# ProProject_GD32__2024-05-09.net
KiCad netlist of a schematic drawn in EasyEDA Pro
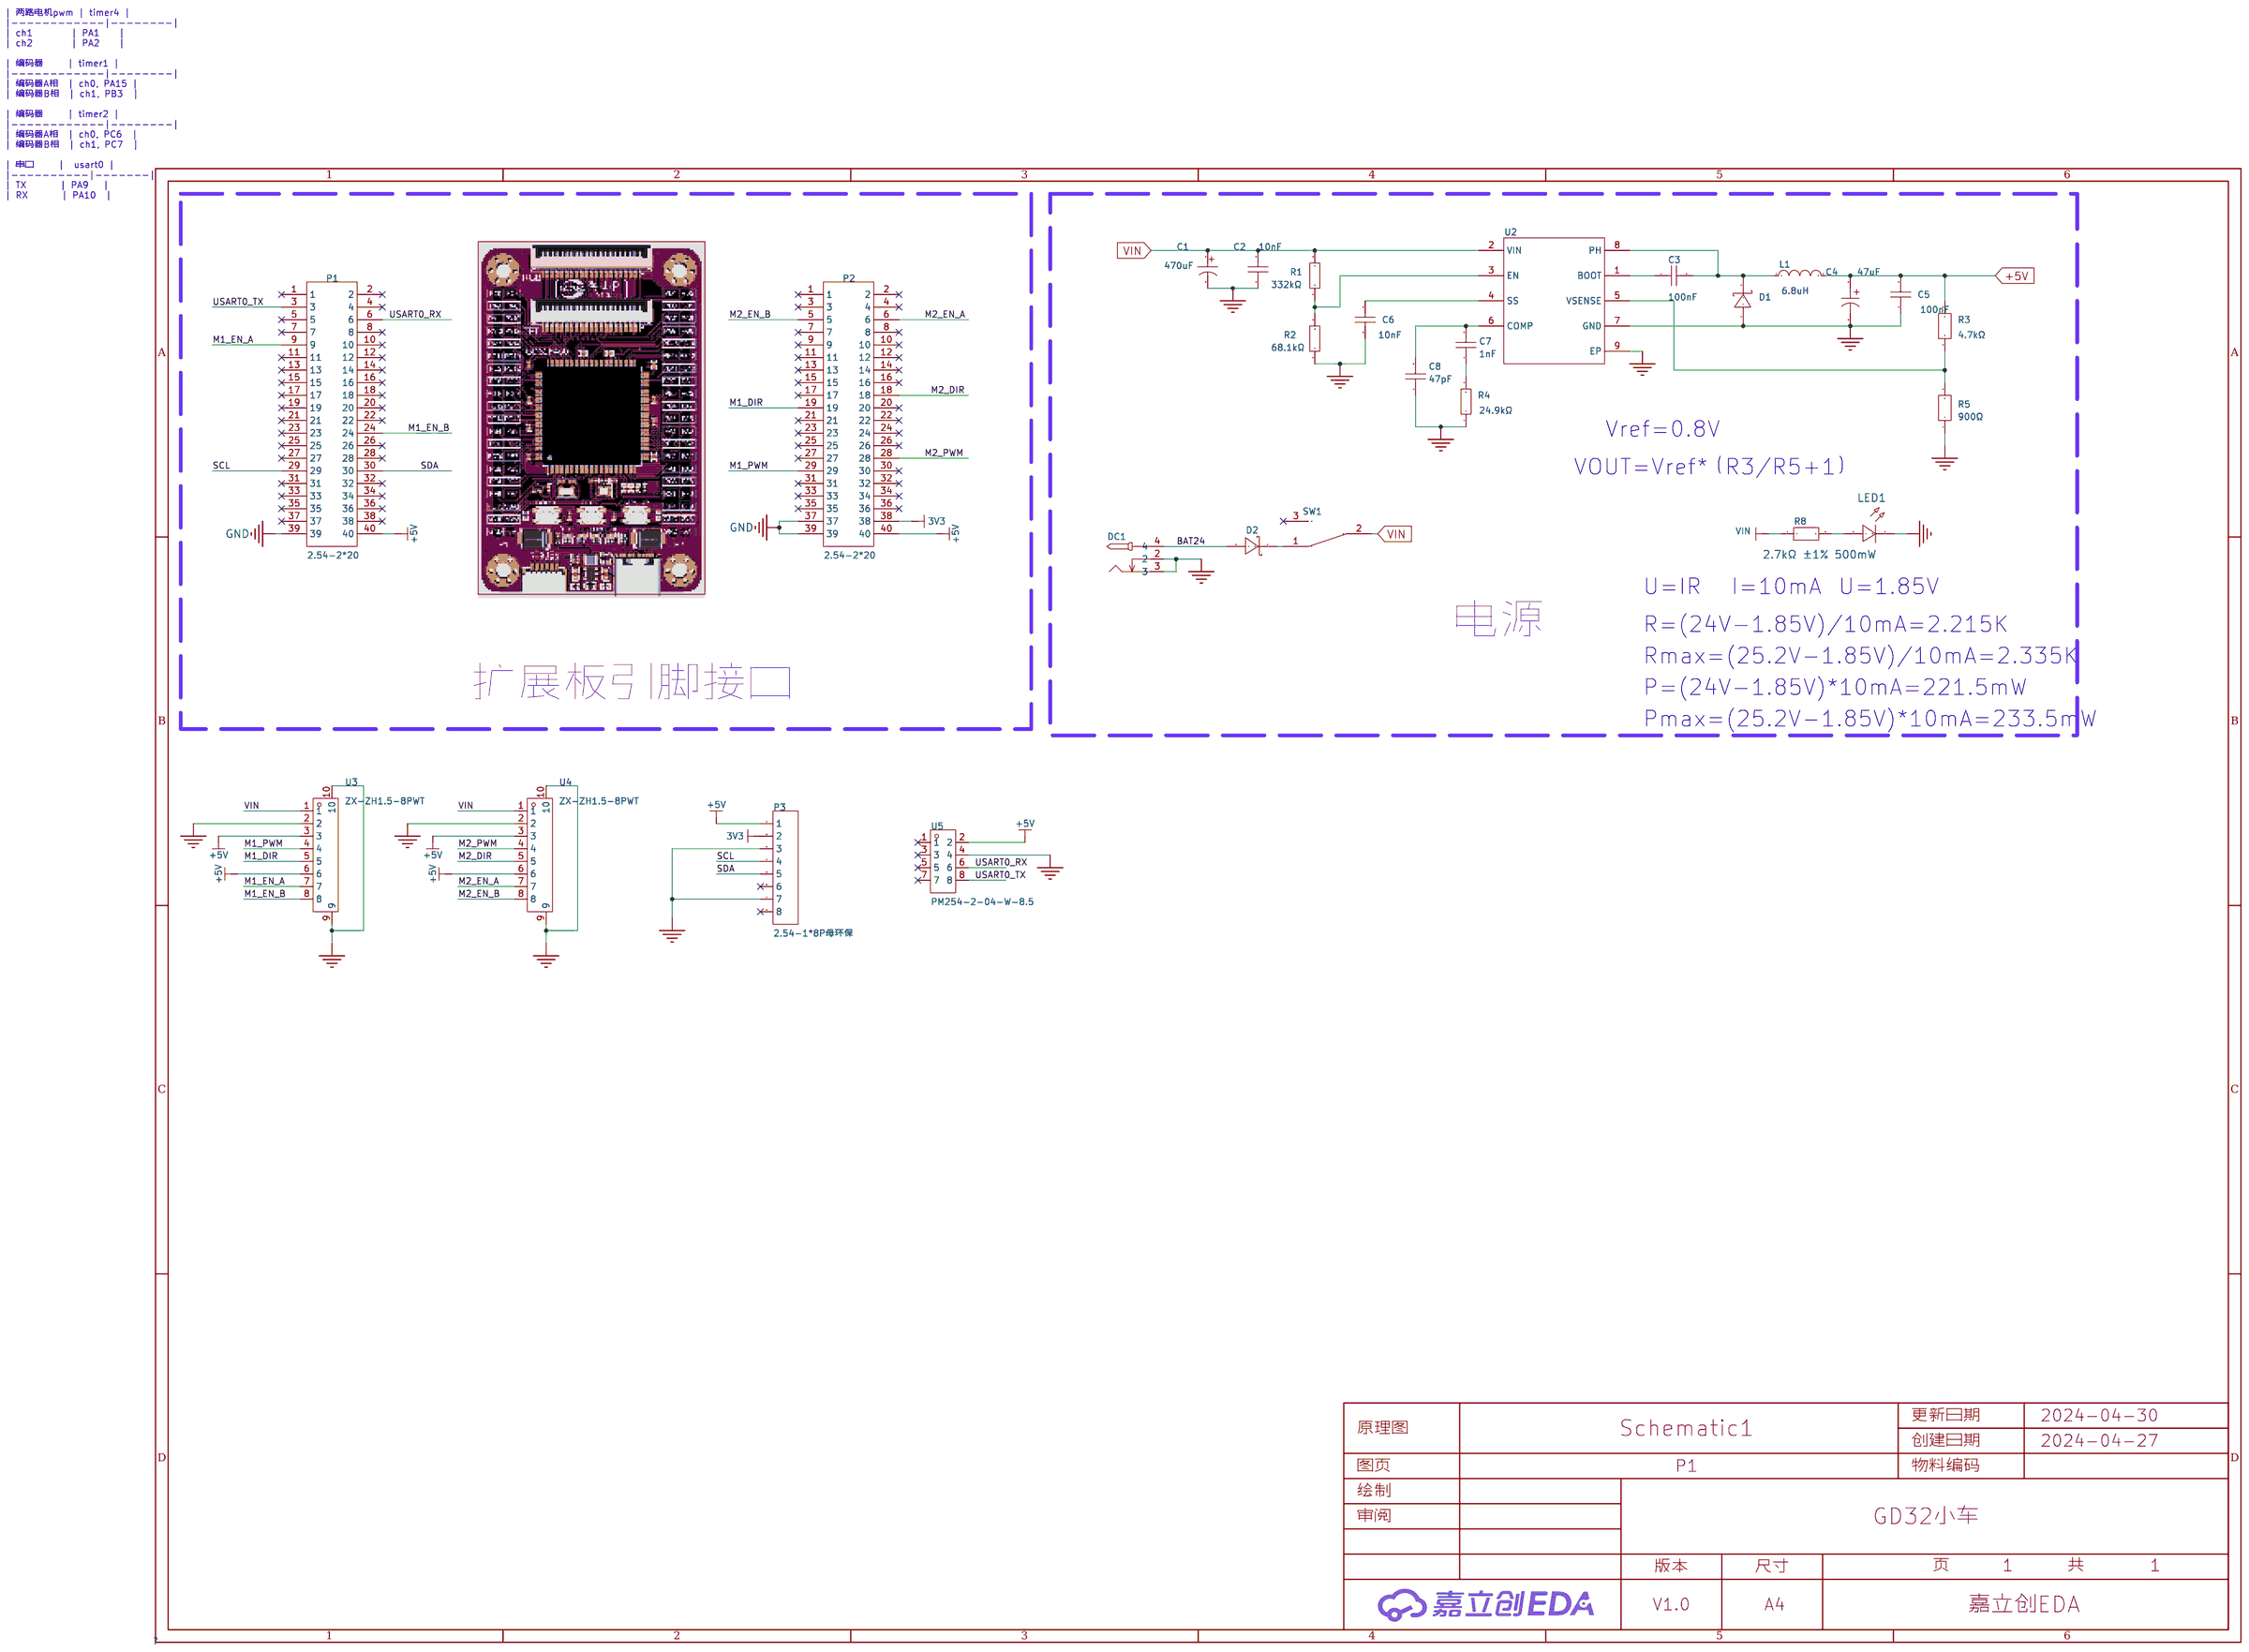
[diagram p0: schematic sheet]

(export (version "E")
  (design (tool "Eeschema 10.0.6"))
  (components
    (comp (ref "C1")
      (value "470uF")
      (footprint "easyedapro:CAP-SMD_BD10.0-L10.3-W10.3-FD")
      (fields (field (name "Manufacturer Part") "RVT1V471M1010") (field (name "Manufacturer") "HONOR(荣誉)"))
      (libsource (lib "easyedapro") (part "RVT1V471M1010"))
    )
    (comp (ref "C2")
      (value "10nF")
      (footprint "easyedapro:C0603")
      (description "容值:10nF;精度:±10%;额定电压:50V;材质(温度系数):X7R;")
      (fields
        (field (name "Manufacturer Part") "CC0603KRX7R9BB103")
        (field (name "Manufacturer") "YAGEO(国巨)")
      )
      (libsource (lib "easyedapro") (part "CC0603KRX7R9BB103"))
    )
    (comp (ref "C3")
      (value "100nF")
      (footprint "easyedapro:C0603")
      (description "容值:100nF;精度:±20%;额定电压:50V;材质(温度系数):Y5V;")
      (fields (field (name "Manufacturer Part") "0603F104M500NT") (field (name "Manufacturer") "FH(风华)"))
      (libsource (lib "easyedapro") (part "0603F104M500NT"))
    )
    (comp (ref "C4")
      (value "47uF")
      (footprint "easyedapro:CAP-SMD_BD6.3-L6.6-W6.6-LS7.2-FD")
      (description "容值:47uF;额定电压:35V;电容体直径:-;电容体长度:-;纹波电流:-;等效串联电阻:-;工作寿命:2000hrs@105°C;")
      (fields
        (field (name "Manufacturer Part") "RVT47UF35V67RV0039")
        (field (name "Manufacturer") "KNSCHA(科尼盛)")
      )
      (libsource (lib "easyedapro") (part "RVT47UF35V67RV0039"))
    )
    (comp (ref "C5")
      (value "100nF")
      (footprint "easyedapro:C0603")
      (description "容值:100nF;精度:±20%;额定电压:50V;材质(温度系数):Y5V;")
      (fields (field (name "Manufacturer Part") "0603F104M500NT") (field (name "Manufacturer") "FH(风华)"))
      (libsource (lib "easyedapro") (part "0603F104M500NT"))
    )
    (comp (ref "C6")
      (value "10nF")
      (footprint "easyedapro:C0603")
      (description "容值:10nF;精度:±10%;额定电压:50V;材质(温度系数):X7R;")
      (fields
        (field (name "Manufacturer Part") "CC0603KRX7R9BB103")
        (field (name "Manufacturer") "YAGEO(国巨)")
      )
      (libsource (lib "easyedapro") (part "CC0603KRX7R9BB103"))
    )
    (comp (ref "C7")
      (value "1nF")
      (footprint "easyedapro:C0603")
      (description "容值:1nF;精度:±10%;额定电压:50V;材质(温度系数):X7R;")
      (fields
        (field (name "Manufacturer Part") "CC0603KRX7R9BB102")
        (field (name "Manufacturer") "YAGEO(国巨)")
      )
      (libsource (lib "easyedapro") (part "CC0603KRX7R9BB102"))
    )
    (comp (ref "C8")
      (value "47pF")
      (footprint "easyedapro:C0603")
      (description "容值:47pF;精度:±5%;额定电压:50V;材质(温度系数):NP0;")
      (fields
        (field (name "Manufacturer Part") "CC0603JRNPO9BN470")
        (field (name "Manufacturer") "YAGEO(国巨)")
      )
      (libsource (lib "easyedapro") (part "CC0603JRNPO9BN470"))
    )
    (comp (ref "D1")
      (value "B340A")
      (footprint "easyedapro:SMA_L4.3-W2.6-LS5.1-RD")
      (description "正向压降(Vf):550mV@3A;直流反向耐压(Vr):40V;平均整流电流(Io):3A;")
      (fields (field (name "Manufacturer") "MDD"))
      (libsource (lib "easyedapro") (part "B340A"))
    )
    (comp (ref "D2")
      (value "SS34")
      (footprint "easyedapro:SMA_L4.4-W2.8-LS5.4-RD")
      (description "直流反向耐压(Vr):40V;平均整流电流(Io):3A;正向压降(Vf):500mV@3A;")
      (fields (field (name "Manufacturer") "BORN(伯恩半导体)"))
      (libsource (lib "easyedapro") (part "SS34_C266553"))
    )
    (comp (ref "DC1")
      (value "DC-005 2.0")
      (footprint "easyedapro:DC-IN-TH_DC-5520-1")
      (description "连接器类型:DC电源插座;安装方式:弯插;触点内径:2mm;触点外径:6.4mm;额定电流:-;额定电压:-;工作温度范围:-;")
      (fields (field (name "Manufacturer") "BOOMELE(博穆精密)"))
      (libsource (lib "easyedapro") (part "DC-005 5.5-2.0MM"))
    )
    (comp (ref "L1")
      (value "6.8uH")
      (footprint "easyedapro:IND-SMD_L7.0-W6.6")
      (description "精度:±20%;直流电阻(DCR):65mΩ;电感值:6.8uH;额定电流:4A;")
      (fields
        (field (name "Manufacturer Part") "TMPC0624H-6R8MG-D")
        (field (name "Manufacturer") "TAI-TECH(台庆)")
      )
      (libsource (lib "easyedapro") (part "TMPC0624H-6R8MG-D"))
    )
    (comp (ref "LED1")
      (value "~")
      (footprint "easyedapro:LED_0805")
      (libsource (lib "easyedapro") (part "LED_R"))
    )
    (comp (ref "P1")
      (value "2.54-2*20")
      (footprint "easyedapro:HDR-TH_40P-P2.54-V-F-R2-C20-S2.54")
      (fields (field (name "Manufacturer") "ZHOURI(洲日)"))
      (libsource (lib "easyedapro") (part "2.54-2*20"))
    )
    (comp (ref "P2")
      (value "2.54-2*20")
      (footprint "easyedapro:HDR-TH_40P-P2.54-V-F-R2-C20-S2.54")
      (fields (field (name "Manufacturer") "ZHOURI(洲日)"))
      (libsource (lib "easyedapro") (part "2.54-2*20"))
    )
    (comp (ref "P3")
      (value "2.54-1*8P母环保")
      (footprint "easyedapro:HDR-TH_8P-P2.54-V-F-1")
      (description "插孔结构:1x8P;间距:2.54mm;行距:-;安装类型:直插;排数:单排;总孔位数:8P;塑高:-;触头材质:-;触头镀层:-;")
      (fields (field (name "Manufacturer") "BOOMELE(博穆精密)"))
      (libsource (lib "easyedapro") (part "Header-Female-2.54_1x8"))
    )
    (comp (ref "R1")
      (value "332kΩ")
      (footprint "easyedapro:R0603")
      (description "精度:±1%;温度系数:±100ppm/°C;阻值:332kΩ;功率:1/10W;最大工作电压:75V;工作温度范围:-55°C~+155°C;")
      (fields
        (field (name "Manufacturer Part") "0603WAF3323T5E")
        (field (name "Manufacturer") "UNI-ROYAL(厚声)")
      )
      (libsource (lib "easyedapro") (part "0603WAF3323T5E"))
    )
    (comp (ref "R2")
      (value "68.1kΩ")
      (footprint "easyedapro:R0603")
      (description "电阻类型:厚膜电阻;阻值:68.1kΩ;精度:±1%;功率:100mW;温度系数:±100ppm/°C;最大工作电压:75V;工作温度范围:-55°C~+155°C;")
      (fields
        (field (name "Manufacturer Part") "0603WAF6812T5E")
        (field (name "Manufacturer") "UNI-ROYAL(厚声)")
      )
      (libsource (lib "easyedapro") (part "0603WAF6812T5E"))
    )
    (comp (ref "R3")
      (value "4.7kΩ")
      (footprint "easyedapro:R0603")
      (fields (field (name "Manufacturer Part") "ERA3ARB472V") (field (name "Manufacturer") "PANASONIC(松下)"))
      (libsource (lib "easyedapro") (part "ERA3ARB472V"))
    )
    (comp (ref "R4")
      (value "24.9kΩ")
      (footprint "easyedapro:R0603")
      (description "精度:±1%;温度系数:±100ppm/°C;阻值:24.9kΩ;功率:1/10W;最大工作电压:75V;工作温度范围:-55°C~+155°C;")
      (fields
        (field (name "Manufacturer Part") "0603WAF2492T5E")
        (field (name "Manufacturer") "UNI-ROYAL(厚声)")
      )
      (libsource (lib "easyedapro") (part "0603WAF2492T5E"))
    )
    (comp (ref "R5")
      (value "900Ω")
      (footprint "easyedapro:R0603")
      (description "电阻类型:厚膜电阻;阻值:900Ω;精度:±1%;功率:100mW;温度系数:±100ppm/°C;最大工作电压:75V;工作温度范围:-55°C~+155°C;")
      (fields
        (field (name "Manufacturer Part") "0603WAF9000T5E")
        (field (name "Manufacturer") "UNI-ROYAL(厚声)")
      )
      (libsource (lib "easyedapro") (part "0603WAF9000T5E"))
    )
    (comp (ref "R8")
      (value "2.7kΩ ±1% 500mW")
      (footprint "easyedapro:R1210")
      (description "电阻类型:厚膜电阻;阻值:2.7kΩ;精度:±1%;功率:500mW;温度系数:±100ppm/°C;最大工作电压:200V;工作温度范围:-55°C~+155°C;")
      (fields
        (field (name "Manufacturer Part") "1210W2F2701T5E")
        (field (name "Manufacturer") "UNI-ROYAL(厚声)")
      )
      (libsource (lib "easyedapro") (part "1210W2F2701T5E"))
    )
    (comp (ref "SW1")
      (value "EG1218")
      (footprint "easyedapro:SW-TH_EG1218")
      (fields (field (name "Manufacturer") "E-Switch"))
      (libsource (lib "easyedapro") (part "EG1218"))
    )
    (comp (ref "U1")
      (value "~")
      (footprint "easyedapro:梁山pi反位置封装")
      (description "Sram芯片排针向上，位置io全显示")
      (libsource (lib "easyedapro") (part "梁山pi反接位置模型"))
    )
    (comp (ref "U2")
      (value "TPS54331DDAR")
      (footprint "easyedapro:SOIC-8_L4.9-W3.9-P1.27-LS6.0-BL-EP")
      (description "功能类型:降压型;输出类型:可调;输入电压:3.5V~28V;输出电压:800mV~25V;输出电流(最大值):3A;")
      (fields (field (name "Manufacturer") "TI(德州仪器)"))
      (libsource (lib "easyedapro") (part "TPS54331DDAR"))
    )
    (comp (ref "U3")
      (value "ZX-ZH1.5-8PWT")
      (footprint "easyedapro:CONN-SMD_8P-P1.50_ZX-ZH1.5-8PWT")
      (fields (field (name "Manufacturer") "Megastar(兆星)"))
      (libsource (lib "easyedapro") (part "ZX-ZH1.5-8-PWT"))
    )
    (comp (ref "U4")
      (value "ZX-ZH1.5-8PWT")
      (footprint "easyedapro:CONN-SMD_8P-P1.50_ZX-ZH1.5-8PWT")
      (fields (field (name "Manufacturer") "Megastar(兆星)"))
      (libsource (lib "easyedapro") (part "ZX-ZH1.5-8-PWT"))
    )
    (comp (ref "U5")
      (value "PM254-2-04-W-8.5")
      (footprint "easyedapro:HDR-TH_8P-P2.54-H-F-R2-C4-W8.5")
      (fields (field (name "Manufacturer") "HCTL(华灿天禄)"))
      (libsource (lib "easyedapro") (part "PM254-2-04-W-8.5"))
    )
  )
  (nets
    (net (code "1") (name "+5V") (class "Default")
      (node (ref "C4") (pin "1") (pinfunction "1_1") (pintype "input"))
      (node (ref "C5") (pin "2") (pinfunction "2_2") (pintype "input"))
      (node (ref "L1") (pin "2") (pinfunction "2_2") (pintype "input"))
      (node (ref "P1") (pin "40") (pinfunction "40_40") (pintype "input"))
      (node (ref "P2") (pin "40") (pinfunction "40_40") (pintype "input"))
      (node (ref "P3") (pin "1") (pinfunction "1_1") (pintype "input"))
      (node (ref "R3") (pin "2") (pinfunction "2_2") (pintype "input"))
      (node (ref "U3") (pin "3") (pinfunction "3_3") (pintype "unspecified"))
      (node (ref "U3") (pin "6") (pinfunction "6_6") (pintype "unspecified"))
      (node (ref "U4") (pin "3") (pinfunction "3_3") (pintype "unspecified"))
      (node (ref "U4") (pin "6") (pinfunction "6_6") (pintype "unspecified"))
      (node (ref "U5") (pin "2") (pinfunction "2_2") (pintype "unspecified"))
    )
    (net (code "2") (name "/BAT24") (class "Default")
      (node (ref "D2") (pin "2") (pinfunction "A_2") (pintype "input"))
      (node (ref "DC1") (pin "4") (pinfunction "4_4") (pintype "input"))
    )
    (net (code "3") (name "/M1_DIR") (class "Default")
      (node (ref "P2") (pin "19") (pinfunction "19_19") (pintype "input"))
      (node (ref "U3") (pin "5") (pinfunction "5_5") (pintype "unspecified"))
    )
    (net (code "4") (name "/M1_EN_A") (class "Default")
      (node (ref "P1") (pin "9") (pinfunction "9_9") (pintype "input"))
      (node (ref "U3") (pin "7") (pinfunction "7_7") (pintype "unspecified"))
    )
    (net (code "5") (name "/M1_EN_B") (class "Default")
      (node (ref "P1") (pin "24") (pinfunction "24_24") (pintype "input"))
      (node (ref "U3") (pin "8") (pinfunction "8_8") (pintype "unspecified"))
    )
    (net (code "6") (name "/M1_PWM") (class "Default")
      (node (ref "P2") (pin "29") (pinfunction "29_29") (pintype "input"))
      (node (ref "U3") (pin "4") (pinfunction "4_4") (pintype "unspecified"))
    )
    (net (code "7") (name "/M2_DIR") (class "Default")
      (node (ref "P2") (pin "18") (pinfunction "18_18") (pintype "input"))
      (node (ref "U4") (pin "5") (pinfunction "5_5") (pintype "unspecified"))
    )
    (net (code "8") (name "/M2_EN_A") (class "Default")
      (node (ref "P2") (pin "6") (pinfunction "6_6") (pintype "input"))
      (node (ref "U4") (pin "7") (pinfunction "7_7") (pintype "unspecified"))
    )
    (net (code "9") (name "/M2_EN_B") (class "Default")
      (node (ref "P2") (pin "5") (pinfunction "5_5") (pintype "input"))
      (node (ref "U4") (pin "8") (pinfunction "8_8") (pintype "unspecified"))
    )
    (net (code "10") (name "/M2_PWM") (class "Default")
      (node (ref "P2") (pin "28") (pinfunction "28_28") (pintype "input"))
      (node (ref "U4") (pin "4") (pinfunction "4_4") (pintype "unspecified"))
    )
    (net (code "11") (name "/SCL") (class "Default")
      (node (ref "P1") (pin "29") (pinfunction "29_29") (pintype "input"))
      (node (ref "P3") (pin "4") (pinfunction "4_4") (pintype "input"))
    )
    (net (code "12") (name "/SDA") (class "Default")
      (node (ref "P1") (pin "30") (pinfunction "30_30") (pintype "input"))
      (node (ref "P3") (pin "5") (pinfunction "5_5") (pintype "input"))
    )
    (net (code "13") (name "/USART0_RX") (class "Default")
      (node (ref "P1") (pin "6") (pinfunction "6_6") (pintype "input"))
      (node (ref "U5") (pin "6") (pinfunction "6_6") (pintype "unspecified"))
    )
    (net (code "14") (name "/USART0_TX") (class "Default")
      (node (ref "P1") (pin "3") (pinfunction "3_3") (pintype "input"))
      (node (ref "U5") (pin "8") (pinfunction "8_8") (pintype "unspecified"))
    )
    (net (code "15") (name "3V3") (class "Default")
      (node (ref "P2") (pin "38") (pinfunction "38_38") (pintype "input"))
      (node (ref "P3") (pin "2") (pinfunction "2_2") (pintype "input"))
    )
    (net (code "16") (name "GND") (class "Default")
      (node (ref "C1") (pin "2") (pinfunction "2_2") (pintype "input"))
      (node (ref "C2") (pin "1") (pinfunction "1_1") (pintype "input"))
      (node (ref "C4") (pin "2") (pinfunction "2_2") (pintype "input"))
      (node (ref "C5") (pin "1") (pinfunction "1_1") (pintype "input"))
      (node (ref "C6") (pin "1") (pinfunction "1_1") (pintype "input"))
      (node (ref "C8") (pin "1") (pinfunction "1_1") (pintype "input"))
      (node (ref "D1") (pin "2") (pinfunction "A_2") (pintype "unspecified"))
      (node (ref "DC1") (pin "2") (pinfunction "2_2") (pintype "input"))
      (node (ref "DC1") (pin "3") (pinfunction "3_3") (pintype "input"))
      (node (ref "LED1") (pin "1") (pinfunction "C_1") (pintype "input"))
      (node (ref "P1") (pin "39") (pinfunction "39_39") (pintype "input"))
      (node (ref "P2") (pin "37") (pinfunction "37_37") (pintype "input"))
      (node (ref "P2") (pin "39") (pinfunction "39_39") (pintype "input"))
      (node (ref "P3") (pin "3") (pinfunction "3_3") (pintype "input"))
      (node (ref "P3") (pin "7") (pinfunction "7_7") (pintype "input"))
      (node (ref "R2") (pin "1") (pinfunction "1_1") (pintype "input"))
      (node (ref "R4") (pin "1") (pinfunction "1_1") (pintype "input"))
      (node (ref "R5") (pin "1") (pinfunction "1_1") (pintype "input"))
      (node (ref "U2") (pin "7") (pinfunction "GND_7") (pintype "unspecified"))
      (node (ref "U2") (pin "9") (pinfunction "EP_9") (pintype "unspecified"))
      (node (ref "U3") (pin "10") (pinfunction "10_10") (pintype "unspecified"))
      (node (ref "U3") (pin "2") (pinfunction "2_2") (pintype "unspecified"))
      (node (ref "U3") (pin "9") (pinfunction "9_9") (pintype "unspecified"))
      (node (ref "U4") (pin "10") (pinfunction "10_10") (pintype "unspecified"))
      (node (ref "U4") (pin "2") (pinfunction "2_2") (pintype "unspecified"))
      (node (ref "U4") (pin "9") (pinfunction "9_9") (pintype "unspecified"))
      (node (ref "U5") (pin "4") (pinfunction "4_4") (pintype "unspecified"))
    )
    (net (code "17") (name "Net-(C7-Pad1)") (class "Default")
      (node (ref "C7") (pin "1") (pinfunction "1_1") (pintype "input"))
      (node (ref "R4") (pin "2") (pinfunction "2_2") (pintype "input"))
    )
    (net (code "18") (name "Net-(D1-K)") (class "Default")
      (node (ref "C3") (pin "2") (pinfunction "2_2") (pintype "input"))
      (node (ref "D1") (pin "1") (pinfunction "K_1") (pintype "unspecified"))
      (node (ref "L1") (pin "1") (pinfunction "1_1") (pintype "input"))
      (node (ref "U2") (pin "8") (pinfunction "PH_8") (pintype "unspecified"))
    )
    (net (code "19") (name "Net-(D2-C)") (class "Default")
      (node (ref "D2") (pin "1") (pinfunction "C_1") (pintype "input"))
      (node (ref "SW1") (pin "1") (pinfunction "1_1") (pintype "input"))
    )
    (net (code "20") (name "Net-(LED1-A)") (class "Default")
      (node (ref "LED1") (pin "2") (pinfunction "A_2") (pintype "input"))
      (node (ref "R8") (pin "2") (pinfunction "2_2") (pintype "unspecified"))
    )
    (net (code "21") (name "Net-(U2-BOOT)") (class "Default")
      (node (ref "C3") (pin "1") (pinfunction "1_1") (pintype "input"))
      (node (ref "U2") (pin "1") (pinfunction "BOOT_1") (pintype "unspecified"))
    )
    (net (code "22") (name "Net-(U2-COMP)") (class "Default")
      (node (ref "C7") (pin "2") (pinfunction "2_2") (pintype "input"))
      (node (ref "C8") (pin "2") (pinfunction "2_2") (pintype "input"))
      (node (ref "U2") (pin "6") (pinfunction "COMP_6") (pintype "unspecified"))
    )
    (net (code "23") (name "Net-(U2-EN)") (class "Default")
      (node (ref "R1") (pin "1") (pinfunction "1_1") (pintype "input"))
      (node (ref "R2") (pin "2") (pinfunction "2_2") (pintype "input"))
      (node (ref "U2") (pin "3") (pinfunction "EN_3") (pintype "unspecified"))
    )
    (net (code "24") (name "Net-(U2-SS)") (class "Default")
      (node (ref "C6") (pin "2") (pinfunction "2_2") (pintype "input"))
      (node (ref "U2") (pin "4") (pinfunction "SS_4") (pintype "unspecified"))
    )
    (net (code "25") (name "Net-(U2-VSENSE)") (class "Default")
      (node (ref "R3") (pin "1") (pinfunction "1_1") (pintype "input"))
      (node (ref "R5") (pin "2") (pinfunction "2_2") (pintype "input"))
      (node (ref "U2") (pin "5") (pinfunction "VSENSE_5") (pintype "unspecified"))
    )
    (net (code "26") (name "VIN") (class "Default")
      (node (ref "C1") (pin "1") (pinfunction "1_1") (pintype "input"))
      (node (ref "C2") (pin "2") (pinfunction "2_2") (pintype "input"))
      (node (ref "R1") (pin "2") (pinfunction "2_2") (pintype "input"))
      (node (ref "R8") (pin "1") (pinfunction "1_1") (pintype "unspecified"))
      (node (ref "SW1") (pin "2") (pinfunction "2_2") (pintype "input"))
      (node (ref "U2") (pin "2") (pinfunction "VIN_2") (pintype "unspecified"))
      (node (ref "U3") (pin "1") (pinfunction "1_1") (pintype "unspecified"))
      (node (ref "U4") (pin "1") (pinfunction "1_1") (pintype "unspecified"))
    )
    (net (code "27") (name "unconnected-(P1-Pad1)") (class "Default")
      (node (ref "P1") (pin "1") (pinfunction "1_1") (pintype "input+no_connect"))
    )
    (net (code "28") (name "unconnected-(P1-Pad2)") (class "Default")
      (node (ref "P1") (pin "2") (pinfunction "2_2") (pintype "input+no_connect"))
    )
    (net (code "29") (name "unconnected-(P1-Pad4)") (class "Default")
      (node (ref "P1") (pin "4") (pinfunction "4_4") (pintype "input+no_connect"))
    )
    (net (code "30") (name "unconnected-(P1-Pad5)") (class "Default")
      (node (ref "P1") (pin "5") (pinfunction "5_5") (pintype "input+no_connect"))
    )
    (net (code "31") (name "unconnected-(P1-Pad7)") (class "Default")
      (node (ref "P1") (pin "7") (pinfunction "7_7") (pintype "input+no_connect"))
    )
    (net (code "32") (name "unconnected-(P1-Pad8)") (class "Default")
      (node (ref "P1") (pin "8") (pinfunction "8_8") (pintype "input+no_connect"))
    )
    (net (code "33") (name "unconnected-(P1-Pad10)") (class "Default")
      (node (ref "P1") (pin "10") (pinfunction "10_10") (pintype "input+no_connect"))
    )
    (net (code "34") (name "unconnected-(P1-Pad11)") (class "Default")
      (node (ref "P1") (pin "11") (pinfunction "11_11") (pintype "input+no_connect"))
    )
    (net (code "35") (name "unconnected-(P1-Pad12)") (class "Default")
      (node (ref "P1") (pin "12") (pinfunction "12_12") (pintype "input+no_connect"))
    )
    (net (code "36") (name "unconnected-(P1-Pad13)") (class "Default")
      (node (ref "P1") (pin "13") (pinfunction "13_13") (pintype "input+no_connect"))
    )
    (net (code "37") (name "unconnected-(P1-Pad14)") (class "Default")
      (node (ref "P1") (pin "14") (pinfunction "14_14") (pintype "input+no_connect"))
    )
    (net (code "38") (name "unconnected-(P1-Pad15)") (class "Default")
      (node (ref "P1") (pin "15") (pinfunction "15_15") (pintype "input+no_connect"))
    )
    (net (code "39") (name "unconnected-(P1-Pad16)") (class "Default")
      (node (ref "P1") (pin "16") (pinfunction "16_16") (pintype "input+no_connect"))
    )
    (net (code "40") (name "unconnected-(P1-Pad17)") (class "Default")
      (node (ref "P1") (pin "17") (pinfunction "17_17") (pintype "input+no_connect"))
    )
    (net (code "41") (name "unconnected-(P1-Pad18)") (class "Default")
      (node (ref "P1") (pin "18") (pinfunction "18_18") (pintype "input+no_connect"))
    )
    (net (code "42") (name "unconnected-(P1-Pad19)") (class "Default")
      (node (ref "P1") (pin "19") (pinfunction "19_19") (pintype "input+no_connect"))
    )
    (net (code "43") (name "unconnected-(P1-Pad20)") (class "Default")
      (node (ref "P1") (pin "20") (pinfunction "20_20") (pintype "input+no_connect"))
    )
    (net (code "44") (name "unconnected-(P1-Pad21)") (class "Default")
      (node (ref "P1") (pin "21") (pinfunction "21_21") (pintype "input+no_connect"))
    )
    (net (code "45") (name "unconnected-(P1-Pad22)") (class "Default")
      (node (ref "P1") (pin "22") (pinfunction "22_22") (pintype "input+no_connect"))
    )
    (net (code "46") (name "unconnected-(P1-Pad23)") (class "Default")
      (node (ref "P1") (pin "23") (pinfunction "23_23") (pintype "input+no_connect"))
    )
    (net (code "47") (name "unconnected-(P1-Pad25)") (class "Default")
      (node (ref "P1") (pin "25") (pinfunction "25_25") (pintype "input+no_connect"))
    )
    (net (code "48") (name "unconnected-(P1-Pad26)") (class "Default")
      (node (ref "P1") (pin "26") (pinfunction "26_26") (pintype "input+no_connect"))
    )
    (net (code "49") (name "unconnected-(P1-Pad27)") (class "Default")
      (node (ref "P1") (pin "27") (pinfunction "27_27") (pintype "input+no_connect"))
    )
    (net (code "50") (name "unconnected-(P1-Pad28)") (class "Default")
      (node (ref "P1") (pin "28") (pinfunction "28_28") (pintype "input+no_connect"))
    )
    (net (code "51") (name "unconnected-(P1-Pad31)") (class "Default")
      (node (ref "P1") (pin "31") (pinfunction "31_31") (pintype "input+no_connect"))
    )
    (net (code "52") (name "unconnected-(P1-Pad32)") (class "Default")
      (node (ref "P1") (pin "32") (pinfunction "32_32") (pintype "input+no_connect"))
    )
    (net (code "53") (name "unconnected-(P1-Pad33)") (class "Default")
      (node (ref "P1") (pin "33") (pinfunction "33_33") (pintype "input+no_connect"))
    )
    (net (code "54") (name "unconnected-(P1-Pad34)") (class "Default")
      (node (ref "P1") (pin "34") (pinfunction "34_34") (pintype "input+no_connect"))
    )
    (net (code "55") (name "unconnected-(P1-Pad35)") (class "Default")
      (node (ref "P1") (pin "35") (pinfunction "35_35") (pintype "input+no_connect"))
    )
    (net (code "56") (name "unconnected-(P1-Pad36)") (class "Default")
      (node (ref "P1") (pin "36") (pinfunction "36_36") (pintype "input+no_connect"))
    )
    (net (code "57") (name "unconnected-(P1-Pad37)") (class "Default")
      (node (ref "P1") (pin "37") (pinfunction "37_37") (pintype "input+no_connect"))
    )
    (net (code "58") (name "unconnected-(P1-Pad38)") (class "Default")
      (node (ref "P1") (pin "38") (pinfunction "38_38") (pintype "input+no_connect"))
    )
    (net (code "59") (name "unconnected-(P2-Pad1)") (class "Default")
      (node (ref "P2") (pin "1") (pinfunction "1_1") (pintype "input+no_connect"))
    )
    (net (code "60") (name "unconnected-(P2-Pad2)") (class "Default")
      (node (ref "P2") (pin "2") (pinfunction "2_2") (pintype "input+no_connect"))
    )
    (net (code "61") (name "unconnected-(P2-Pad3)") (class "Default")
      (node (ref "P2") (pin "3") (pinfunction "3_3") (pintype "input+no_connect"))
    )
    (net (code "62") (name "unconnected-(P2-Pad4)") (class "Default")
      (node (ref "P2") (pin "4") (pinfunction "4_4") (pintype "input+no_connect"))
    )
    (net (code "63") (name "unconnected-(P2-Pad7)") (class "Default")
      (node (ref "P2") (pin "7") (pinfunction "7_7") (pintype "input+no_connect"))
    )
    (net (code "64") (name "unconnected-(P2-Pad8)") (class "Default")
      (node (ref "P2") (pin "8") (pinfunction "8_8") (pintype "input+no_connect"))
    )
    (net (code "65") (name "unconnected-(P2-Pad9)") (class "Default")
      (node (ref "P2") (pin "9") (pinfunction "9_9") (pintype "input+no_connect"))
    )
    (net (code "66") (name "unconnected-(P2-Pad10)") (class "Default")
      (node (ref "P2") (pin "10") (pinfunction "10_10") (pintype "input+no_connect"))
    )
    (net (code "67") (name "unconnected-(P2-Pad11)") (class "Default")
      (node (ref "P2") (pin "11") (pinfunction "11_11") (pintype "input+no_connect"))
    )
    (net (code "68") (name "unconnected-(P2-Pad12)") (class "Default")
      (node (ref "P2") (pin "12") (pinfunction "12_12") (pintype "input+no_connect"))
    )
    (net (code "69") (name "unconnected-(P2-Pad13)") (class "Default")
      (node (ref "P2") (pin "13") (pinfunction "13_13") (pintype "input+no_connect"))
    )
    (net (code "70") (name "unconnected-(P2-Pad14)") (class "Default")
      (node (ref "P2") (pin "14") (pinfunction "14_14") (pintype "input+no_connect"))
    )
    (net (code "71") (name "unconnected-(P2-Pad15)") (class "Default")
      (node (ref "P2") (pin "15") (pinfunction "15_15") (pintype "input+no_connect"))
    )
    (net (code "72") (name "unconnected-(P2-Pad16)") (class "Default")
      (node (ref "P2") (pin "16") (pinfunction "16_16") (pintype "input+no_connect"))
    )
    (net (code "73") (name "unconnected-(P2-Pad17)") (class "Default")
      (node (ref "P2") (pin "17") (pinfunction "17_17") (pintype "input+no_connect"))
    )
    (net (code "74") (name "unconnected-(P2-Pad20)") (class "Default")
      (node (ref "P2") (pin "20") (pinfunction "20_20") (pintype "input+no_connect"))
    )
    (net (code "75") (name "unconnected-(P2-Pad21)") (class "Default")
      (node (ref "P2") (pin "21") (pinfunction "21_21") (pintype "input+no_connect"))
    )
    (net (code "76") (name "unconnected-(P2-Pad22)") (class "Default")
      (node (ref "P2") (pin "22") (pinfunction "22_22") (pintype "input+no_connect"))
    )
    (net (code "77") (name "unconnected-(P2-Pad23)") (class "Default")
      (node (ref "P2") (pin "23") (pinfunction "23_23") (pintype "input+no_connect"))
    )
    (net (code "78") (name "unconnected-(P2-Pad24)") (class "Default")
      (node (ref "P2") (pin "24") (pinfunction "24_24") (pintype "input+no_connect"))
    )
    (net (code "79") (name "unconnected-(P2-Pad25)") (class "Default")
      (node (ref "P2") (pin "25") (pinfunction "25_25") (pintype "input+no_connect"))
    )
    (net (code "80") (name "unconnected-(P2-Pad26)") (class "Default")
      (node (ref "P2") (pin "26") (pinfunction "26_26") (pintype "input+no_connect"))
    )
    (net (code "81") (name "unconnected-(P2-Pad27)") (class "Default")
      (node (ref "P2") (pin "27") (pinfunction "27_27") (pintype "input+no_connect"))
    )
    (net (code "82") (name "unconnected-(P2-Pad30)") (class "Default")
      (node (ref "P2") (pin "30") (pinfunction "30_30") (pintype "input+no_connect"))
    )
    (net (code "83") (name "unconnected-(P2-Pad31)") (class "Default")
      (node (ref "P2") (pin "31") (pinfunction "31_31") (pintype "input+no_connect"))
    )
    (net (code "84") (name "unconnected-(P2-Pad32)") (class "Default")
      (node (ref "P2") (pin "32") (pinfunction "32_32") (pintype "input+no_connect"))
    )
    (net (code "85") (name "unconnected-(P2-Pad33)") (class "Default")
      (node (ref "P2") (pin "33") (pinfunction "33_33") (pintype "input+no_connect"))
    )
    (net (code "86") (name "unconnected-(P2-Pad34)") (class "Default")
      (node (ref "P2") (pin "34") (pinfunction "34_34") (pintype "input+no_connect"))
    )
    (net (code "87") (name "unconnected-(P2-Pad35)") (class "Default")
      (node (ref "P2") (pin "35") (pinfunction "35_35") (pintype "input+no_connect"))
    )
    (net (code "88") (name "unconnected-(P2-Pad36)") (class "Default")
      (node (ref "P2") (pin "36") (pinfunction "36_36") (pintype "input+no_connect"))
    )
    (net (code "89") (name "unconnected-(P3-Pad6)") (class "Default")
      (node (ref "P3") (pin "6") (pinfunction "6_6") (pintype "input+no_connect"))
    )
    (net (code "90") (name "unconnected-(P3-Pad8)") (class "Default")
      (node (ref "P3") (pin "8") (pinfunction "8_8") (pintype "input+no_connect"))
    )
    (net (code "91") (name "unconnected-(SW1-Pad3)") (class "Default")
      (node (ref "SW1") (pin "3") (pinfunction "3_3") (pintype "input+no_connect"))
    )
    (net (code "92") (name "unconnected-(U5-Pad1)") (class "Default")
      (node (ref "U5") (pin "1") (pinfunction "1_1") (pintype "unspecified+no_connect"))
    )
    (net (code "93") (name "unconnected-(U5-Pad3)") (class "Default")
      (node (ref "U5") (pin "3") (pinfunction "3_3") (pintype "unspecified+no_connect"))
    )
    (net (code "94") (name "unconnected-(U5-Pad5)") (class "Default")
      (node (ref "U5") (pin "5") (pinfunction "5_5") (pintype "unspecified+no_connect"))
    )
    (net (code "95") (name "unconnected-(U5-Pad7)") (class "Default")
      (node (ref "U5") (pin "7") (pinfunction "7_7") (pintype "unspecified+no_connect"))
    )
  )
)
